# Sheet2.net
KiCad netlist of a schematic drawn in Altium Designer
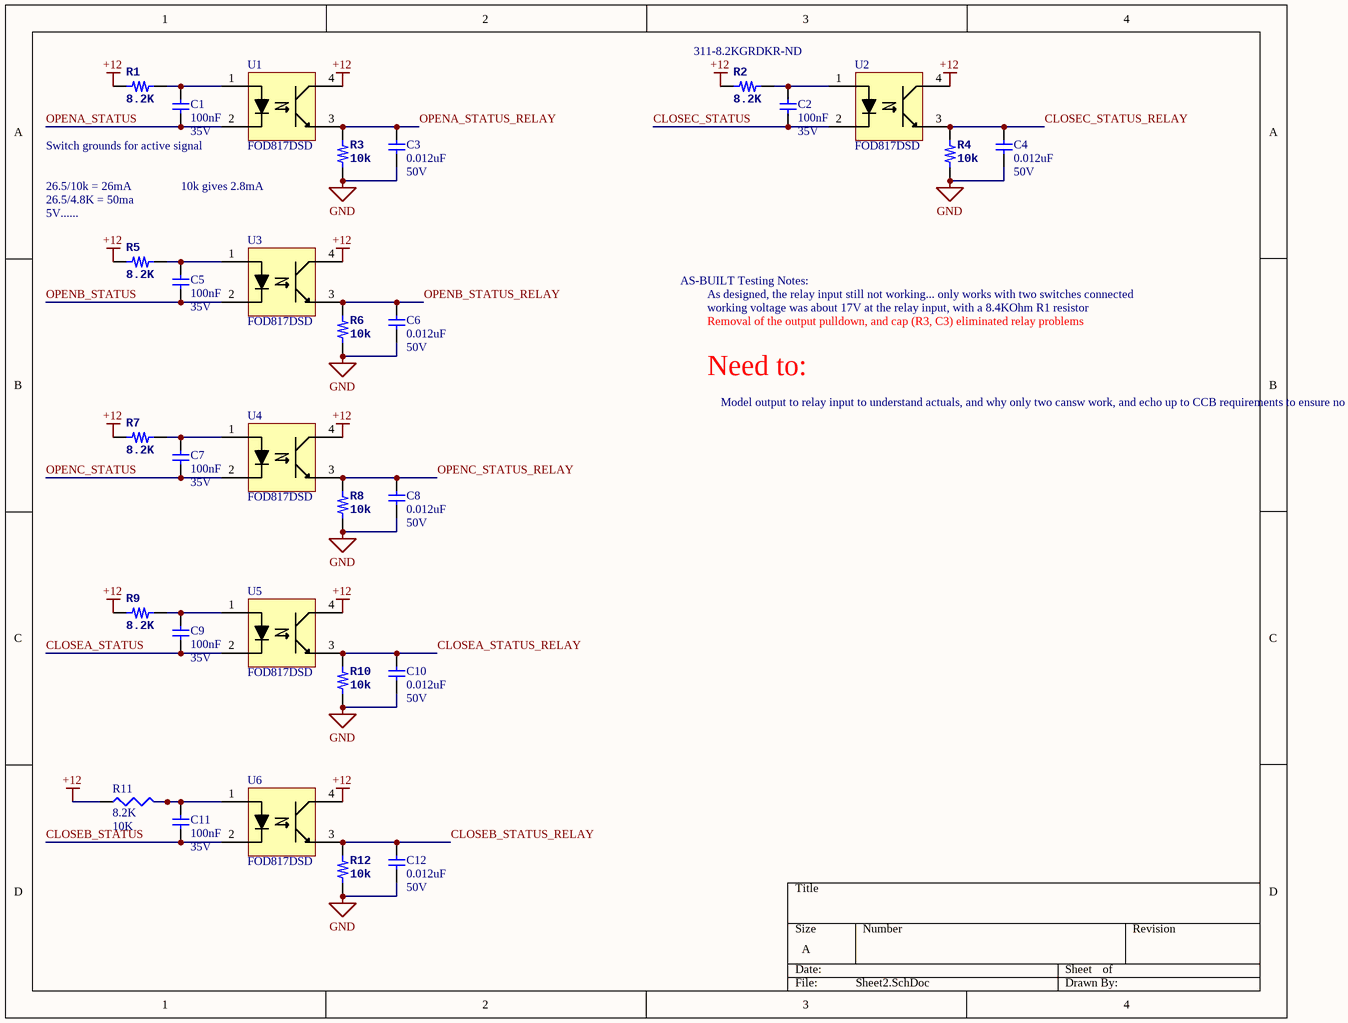
[diagram p0: Sheet2.SchDoc]

(export (version "E")
  (design (tool "Eeschema 10.0.6"))
  (components
    (comp (ref "C1")
      (value "100nF")
      (footprint "C0603N")
      (description "CAP CER 10% 0603")
      (fields (field (name "PART NUMBER") "?") (field (name "VOLTAGE") "35V"))
      (libsource (lib "ASD_MASTER") (part "CAP_0603"))
    )
    (comp (ref "C2")
      (value "100nF")
      (footprint "C0603N")
      (description "CAP CER 10% 0603")
      (fields (field (name "PART NUMBER") "?") (field (name "VOLTAGE") "35V"))
      (libsource (lib "ASD_MASTER") (part "CAP_0603"))
    )
    (comp (ref "C3")
      (value "0.012uF")
      (footprint "C0805K")
      (description "CAP CER 10% 0805")
      (fields (field (name "PARTNUMBER") "?") (field (name "VOLTAGE") "50V"))
      (libsource (lib "ASD_MASTER") (part "CAP_0805"))
    )
    (comp (ref "C4")
      (value "0.012uF")
      (footprint "C0805K")
      (description "CAP CER 10% 0805")
      (fields (field (name "PARTNUMBER") "?") (field (name "VOLTAGE") "50V"))
      (libsource (lib "ASD_MASTER") (part "CAP_0805"))
    )
    (comp (ref "C5")
      (value "100nF")
      (footprint "C0603N")
      (description "CAP CER 10% 0603")
      (fields (field (name "PART NUMBER") "?") (field (name "VOLTAGE") "35V"))
      (libsource (lib "ASD_MASTER") (part "CAP_0603"))
    )
    (comp (ref "C6")
      (value "0.012uF")
      (footprint "C0805K")
      (description "CAP CER 10% 0805")
      (fields (field (name "PARTNUMBER") "?") (field (name "VOLTAGE") "50V"))
      (libsource (lib "ASD_MASTER") (part "CAP_0805"))
    )
    (comp (ref "C7")
      (value "100nF")
      (footprint "C0603N")
      (description "CAP CER 10% 0603")
      (fields (field (name "PART NUMBER") "?") (field (name "VOLTAGE") "35V"))
      (libsource (lib "ASD_MASTER") (part "CAP_0603"))
    )
    (comp (ref "C8")
      (value "0.012uF")
      (footprint "C0805K")
      (description "CAP CER 10% 0805")
      (fields (field (name "PARTNUMBER") "?") (field (name "VOLTAGE") "50V"))
      (libsource (lib "ASD_MASTER") (part "CAP_0805"))
    )
    (comp (ref "C9")
      (value "100nF")
      (footprint "C0603N")
      (description "CAP CER 10% 0603")
      (fields (field (name "PART NUMBER") "?") (field (name "VOLTAGE") "35V"))
      (libsource (lib "ASD_MASTER") (part "CAP_0603"))
    )
    (comp (ref "C10")
      (value "0.012uF")
      (footprint "C0805K")
      (description "CAP CER 10% 0805")
      (fields (field (name "PARTNUMBER") "?") (field (name "VOLTAGE") "50V"))
      (libsource (lib "ASD_MASTER") (part "CAP_0805"))
    )
    (comp (ref "C11")
      (value "100nF")
      (footprint "C0603N")
      (description "CAP CER 10% 0603")
      (fields (field (name "PART NUMBER") "?") (field (name "VOLTAGE") "35V"))
      (libsource (lib "ASD_MASTER") (part "CAP_0603"))
    )
    (comp (ref "C12")
      (value "0.012uF")
      (footprint "C0805K")
      (description "CAP CER 10% 0805")
      (fields (field (name "PARTNUMBER") "?") (field (name "VOLTAGE") "50V"))
      (libsource (lib "ASD_MASTER") (part "CAP_0805"))
    )
    (comp (ref "R1")
      (value "8.2K")
      (footprint "R0603N")
      (description "RES SMD 1/10W 0603 1%")
      (fields (field (name "MANUFACTURER") "?") (field (name "POWER") "1/10W"))
      (libsource (lib "ASD_MASTER") (part "RES_1/10W_0603_1%"))
    )
    (comp (ref "R2")
      (value "8.2K")
      (footprint "R0603N")
      (description "RES SMD 1/10W 0603 1%")
      (fields
        (field (name "MANUFACTURER") "?")
        (field (name "POWER") "1/10W")
        (field (name "SUPPLIER PART NUMBER 1") "311-8.2KGRDKR-ND")
      )
      (libsource (lib "ASD_MASTER") (part "RES_1/10W_0603_1%"))
    )
    (comp (ref "R3")
      (value "10k")
      (footprint "R0603N")
      (description "RES SMD 1/10W 0603 0.1%")
      (fields (field (name "MANUFACTURER") "?") (field (name "POWER") "1/10W"))
      (libsource (lib "ASD_MASTER") (part "RES_1/10W_0603_0.1%"))
    )
    (comp (ref "R4")
      (value "10k")
      (footprint "R0603N")
      (description "RES SMD 1/10W 0603 0.1%")
      (fields (field (name "MANUFACTURER") "?") (field (name "POWER") "1/10W"))
      (libsource (lib "ASD_MASTER") (part "RES_1/10W_0603_0.1%"))
    )
    (comp (ref "R5")
      (value "8.2K")
      (footprint "R0603N")
      (description "RES SMD 1/10W 0603 1%")
      (fields (field (name "MANUFACTURER") "?") (field (name "POWER") "1/10W"))
      (libsource (lib "ASD_MASTER") (part "RES_1/10W_0603_1%"))
    )
    (comp (ref "R6")
      (value "10k")
      (footprint "R0603N")
      (description "RES SMD 1/10W 0603 0.1%")
      (fields (field (name "MANUFACTURER") "?") (field (name "POWER") "1/10W"))
      (libsource (lib "ASD_MASTER") (part "RES_1/10W_0603_0.1%"))
    )
    (comp (ref "R7")
      (value "8.2K")
      (footprint "R0603N")
      (description "RES SMD 1/10W 0603 1%")
      (fields (field (name "MANUFACTURER") "?") (field (name "POWER") "1/10W"))
      (libsource (lib "ASD_MASTER") (part "RES_1/10W_0603_1%"))
    )
    (comp (ref "R8")
      (value "10k")
      (footprint "R0603N")
      (description "RES SMD 1/10W 0603 0.1%")
      (fields (field (name "MANUFACTURER") "?") (field (name "POWER") "1/10W"))
      (libsource (lib "ASD_MASTER") (part "RES_1/10W_0603_0.1%"))
    )
    (comp (ref "R9")
      (value "8.2K")
      (footprint "R0603N")
      (description "RES SMD 1/10W 0603 1%")
      (fields (field (name "MANUFACTURER") "?") (field (name "POWER") "1/10W"))
      (libsource (lib "ASD_MASTER") (part "RES_1/10W_0603_1%"))
    )
    (comp (ref "R10")
      (value "10k")
      (footprint "R0603N")
      (description "RES SMD 1/10W 0603 0.1%")
      (fields (field (name "MANUFACTURER") "?") (field (name "POWER") "1/10W"))
      (libsource (lib "ASD_MASTER") (part "RES_1/10W_0603_0.1%"))
    )
    (comp (ref "R11")
      (value "8.2K")
      (footprint "J1-0603")
      (description "Resistor")
      (fields (field (name "ALTIUM_VALUE") "10K") (field (name "PUBLISHER") "Altium Limited"))
      (libsource (lib "Miscellaneous Devices") (part "Res3"))
    )
    (comp (ref "R12")
      (value "10k")
      (footprint "R0603N")
      (description "RES SMD 1/10W 0603 0.1%")
      (fields (field (name "MANUFACTURER") "?") (field (name "POWER") "1/10W"))
      (libsource (lib "ASD_MASTER") (part "RES_1/10W_0603_0.1%"))
    )
    (comp (ref "U1")
      (value "FOD817DSD")
      (footprint "4-SMD GullWing")
      (description "OPTOISOLATOR 5KV TRANSISTOR 4SMD")
      (fields (field (name "MANUFACTURER") "Fairchild"))
      (libsource (lib "ASD") (part "108-00030-001"))
    )
    (comp (ref "U2")
      (value "FOD817DSD")
      (footprint "4-SMD GullWing")
      (description "OPTOISOLATOR 5KV TRANSISTOR 4SMD")
      (fields (field (name "MANUFACTURER") "Fairchild"))
      (libsource (lib "ASD") (part "108-00030-001"))
    )
    (comp (ref "U3")
      (value "FOD817DSD")
      (footprint "4-SMD GullWing")
      (description "OPTOISOLATOR 5KV TRANSISTOR 4SMD")
      (fields (field (name "MANUFACTURER") "Fairchild"))
      (libsource (lib "ASD") (part "108-00030-001"))
    )
    (comp (ref "U4")
      (value "FOD817DSD")
      (footprint "4-SMD GullWing")
      (description "OPTOISOLATOR 5KV TRANSISTOR 4SMD")
      (fields (field (name "MANUFACTURER") "Fairchild"))
      (libsource (lib "ASD") (part "108-00030-001"))
    )
    (comp (ref "U5")
      (value "FOD817DSD")
      (footprint "4-SMD GullWing")
      (description "OPTOISOLATOR 5KV TRANSISTOR 4SMD")
      (fields (field (name "MANUFACTURER") "Fairchild"))
      (libsource (lib "ASD") (part "108-00030-001"))
    )
    (comp (ref "U6")
      (value "FOD817DSD")
      (footprint "4-SMD GullWing")
      (description "OPTOISOLATOR 5KV TRANSISTOR 4SMD")
      (fields (field (name "MANUFACTURER") "Fairchild"))
      (libsource (lib "ASD") (part "108-00030-001"))
    )
  )
  (nets
    (net (code "1") (name "+12") (class "Default")
      (node (ref "R1") (pin "2") (pinfunction "2_2") (pintype "passive"))
      (node (ref "R11") (pin "1") (pinfunction "1_1") (pintype "passive"))
      (node (ref "R2") (pin "2") (pinfunction "2_2") (pintype "passive"))
      (node (ref "R5") (pin "2") (pinfunction "2_2") (pintype "passive"))
      (node (ref "R7") (pin "2") (pinfunction "2_2") (pintype "passive"))
      (node (ref "R9") (pin "2") (pinfunction "2_2") (pintype "passive"))
      (node (ref "U1") (pin "4") (pinfunction "C_4") (pintype "passive"))
      (node (ref "U2") (pin "4") (pinfunction "C_4") (pintype "passive"))
      (node (ref "U3") (pin "4") (pinfunction "C_4") (pintype "passive"))
      (node (ref "U4") (pin "4") (pinfunction "C_4") (pintype "passive"))
      (node (ref "U5") (pin "4") (pinfunction "C_4") (pintype "passive"))
      (node (ref "U6") (pin "4") (pinfunction "C_4") (pintype "passive"))
    )
    (net (code "2") (name "/CLOSEA_STATUS") (class "Default")
      (node (ref "C9") (pin "2") (pinfunction "2_2") (pintype "passive"))
      (node (ref "U5") (pin "2") (pinfunction "C_2") (pintype "passive"))
    )
    (net (code "3") (name "/CLOSEA_STATUS_RELAY") (class "Default")
      (node (ref "C10") (pin "1") (pinfunction "1_1") (pintype "passive"))
      (node (ref "R10") (pin "2") (pinfunction "2_2") (pintype "passive"))
      (node (ref "U5") (pin "3") (pinfunction "E_3") (pintype "passive"))
    )
    (net (code "4") (name "/CLOSEB_STATUS") (class "Default")
      (node (ref "C11") (pin "2") (pinfunction "2_2") (pintype "passive"))
      (node (ref "U6") (pin "2") (pinfunction "C_2") (pintype "passive"))
    )
    (net (code "5") (name "/CLOSEB_STATUS_RELAY") (class "Default")
      (node (ref "C12") (pin "1") (pinfunction "1_1") (pintype "passive"))
      (node (ref "R12") (pin "2") (pinfunction "2_2") (pintype "passive"))
      (node (ref "U6") (pin "3") (pinfunction "E_3") (pintype "passive"))
    )
    (net (code "6") (name "/CLOSEC_STATUS") (class "Default")
      (node (ref "C2") (pin "2") (pinfunction "2_2") (pintype "passive"))
      (node (ref "U2") (pin "2") (pinfunction "C_2") (pintype "passive"))
    )
    (net (code "7") (name "/CLOSEC_STATUS_RELAY") (class "Default")
      (node (ref "C4") (pin "1") (pinfunction "1_1") (pintype "passive"))
      (node (ref "R4") (pin "2") (pinfunction "2_2") (pintype "passive"))
      (node (ref "U2") (pin "3") (pinfunction "E_3") (pintype "passive"))
    )
    (net (code "8") (name "/OPENA_STATUS") (class "Default")
      (node (ref "C1") (pin "2") (pinfunction "2_2") (pintype "passive"))
      (node (ref "U1") (pin "2") (pinfunction "C_2") (pintype "passive"))
    )
    (net (code "9") (name "/OPENA_STATUS_RELAY") (class "Default")
      (node (ref "C3") (pin "1") (pinfunction "1_1") (pintype "passive"))
      (node (ref "R3") (pin "2") (pinfunction "2_2") (pintype "passive"))
      (node (ref "U1") (pin "3") (pinfunction "E_3") (pintype "passive"))
    )
    (net (code "10") (name "/OPENB_STATUS") (class "Default")
      (node (ref "C5") (pin "2") (pinfunction "2_2") (pintype "passive"))
      (node (ref "U3") (pin "2") (pinfunction "C_2") (pintype "passive"))
    )
    (net (code "11") (name "/OPENB_STATUS_RELAY") (class "Default")
      (node (ref "C6") (pin "1") (pinfunction "1_1") (pintype "passive"))
      (node (ref "R6") (pin "2") (pinfunction "2_2") (pintype "passive"))
      (node (ref "U3") (pin "3") (pinfunction "E_3") (pintype "passive"))
    )
    (net (code "12") (name "/OPENC_STATUS") (class "Default")
      (node (ref "C7") (pin "2") (pinfunction "2_2") (pintype "passive"))
      (node (ref "U4") (pin "2") (pinfunction "C_2") (pintype "passive"))
    )
    (net (code "13") (name "/OPENC_STATUS_RELAY") (class "Default")
      (node (ref "C8") (pin "1") (pinfunction "1_1") (pintype "passive"))
      (node (ref "R8") (pin "2") (pinfunction "2_2") (pintype "passive"))
      (node (ref "U4") (pin "3") (pinfunction "E_3") (pintype "passive"))
    )
    (net (code "14") (name "GND") (class "Default")
      (node (ref "C10") (pin "2") (pinfunction "2_2") (pintype "passive"))
      (node (ref "C12") (pin "2") (pinfunction "2_2") (pintype "passive"))
      (node (ref "C3") (pin "2") (pinfunction "2_2") (pintype "passive"))
      (node (ref "C4") (pin "2") (pinfunction "2_2") (pintype "passive"))
      (node (ref "C6") (pin "2") (pinfunction "2_2") (pintype "passive"))
      (node (ref "C8") (pin "2") (pinfunction "2_2") (pintype "passive"))
      (node (ref "R10") (pin "1") (pinfunction "1_1") (pintype "passive"))
      (node (ref "R12") (pin "1") (pinfunction "1_1") (pintype "passive"))
      (node (ref "R3") (pin "1") (pinfunction "1_1") (pintype "passive"))
      (node (ref "R4") (pin "1") (pinfunction "1_1") (pintype "passive"))
      (node (ref "R6") (pin "1") (pinfunction "1_1") (pintype "passive"))
      (node (ref "R8") (pin "1") (pinfunction "1_1") (pintype "passive"))
    )
    (net (code "15") (name "Net-(U1-A)") (class "Default")
      (node (ref "C1") (pin "1") (pinfunction "1_1") (pintype "passive"))
      (node (ref "R1") (pin "1") (pinfunction "1_1") (pintype "passive"))
      (node (ref "U1") (pin "1") (pinfunction "A_1") (pintype "passive"))
    )
    (net (code "16") (name "Net-(U2-A)") (class "Default")
      (node (ref "C2") (pin "1") (pinfunction "1_1") (pintype "passive"))
      (node (ref "R2") (pin "1") (pinfunction "1_1") (pintype "passive"))
      (node (ref "U2") (pin "1") (pinfunction "A_1") (pintype "passive"))
    )
    (net (code "17") (name "Net-(U3-A)") (class "Default")
      (node (ref "C5") (pin "1") (pinfunction "1_1") (pintype "passive"))
      (node (ref "R5") (pin "1") (pinfunction "1_1") (pintype "passive"))
      (node (ref "U3") (pin "1") (pinfunction "A_1") (pintype "passive"))
    )
    (net (code "18") (name "Net-(U4-A)") (class "Default")
      (node (ref "C7") (pin "1") (pinfunction "1_1") (pintype "passive"))
      (node (ref "R7") (pin "1") (pinfunction "1_1") (pintype "passive"))
      (node (ref "U4") (pin "1") (pinfunction "A_1") (pintype "passive"))
    )
    (net (code "19") (name "Net-(U5-A)") (class "Default")
      (node (ref "C9") (pin "1") (pinfunction "1_1") (pintype "passive"))
      (node (ref "R9") (pin "1") (pinfunction "1_1") (pintype "passive"))
      (node (ref "U5") (pin "1") (pinfunction "A_1") (pintype "passive"))
    )
    (net (code "20") (name "Net-(U6-A)") (class "Default")
      (node (ref "C11") (pin "1") (pinfunction "1_1") (pintype "passive"))
      (node (ref "R11") (pin "2") (pinfunction "2_2") (pintype "passive"))
      (node (ref "U6") (pin "1") (pinfunction "A_1") (pintype "passive"))
    )
  )
)
